# smd_missing_pulse_detector_sot23.net
KiCad netlist of a schematic drawn in EAGLE
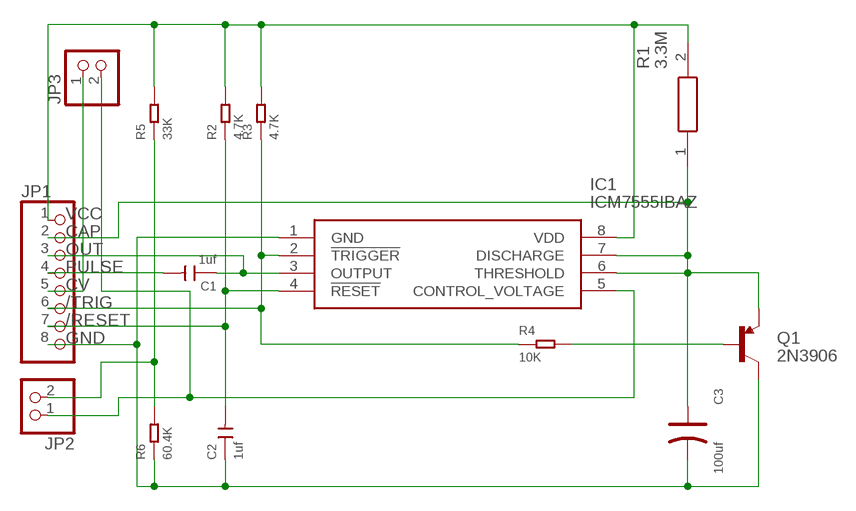
[diagram p0: schematic, sheet 1]

(export (version "E")
  (design (tool "Eeschema 10.0.6"))
  (components
    (comp (ref "C1")
      (value "1uf")
      (footprint "eagle-import:C0805")
      (fields (field (name "MPN") "CC0805KKX7R8BB105"))
      (libsource (lib "eagle-import") (part "CERAMIC-1UF-25V-10%-X7R(0805)"))
    )
    (comp (ref "C2")
      (value "1uf")
      (footprint "eagle-import:C0805")
      (fields (field (name "MPN") "CC0805KKX7R8BB105"))
      (libsource (lib "eagle-import") (part "CERAMIC-1UF-25V-10%-X7R(0805)"))
    )
    (comp (ref "C3")
      (value "100uf")
      (footprint "eagle-import:AVX-B")
      (fields (field (name "MPN") "TAJB107M010#NJ"))
      (libsource (lib "eagle-import") (part "TANTALUM-SMD-100UF-10V(AVX-B)"))
    )
    (comp (ref "IC1")
      (value "ICM7555IBAZ")
      (footprint "eagle-import:SOIC127P600X175-8N")
      (fields (field (name "MOUSER_PART_NUMBER") "968-ICM7555IBAZ"))
      (libsource (lib "eagle-import") (part "ICM7555IBAZ"))
    )
    (comp (ref "JP1")
      (value "PINHD-1X8")
      (footprint "eagle-import:1X08")
      (libsource (lib "eagle-import") (part "PINHD-1X8"))
    )
    (comp (ref "JP2")
      (value "PINHD-1X2")
      (footprint "eagle-import:1X02")
      (libsource (lib "eagle-import") (part "PINHD-1X2"))
    )
    (comp (ref "JP3")
      (value "PINHD-1X2")
      (footprint "eagle-import:1X02")
      (libsource (lib "eagle-import") (part "PINHD-1X2"))
    )
    (comp (ref "Q1")
      (value "2N3906")
      (footprint "eagle-import:SOT23-3")
      (libsource (lib "eagle-import") (part "TRANSISTOR_PNPPMBT3906"))
    )
    (comp (ref "R1")
      (value "3.3M")
      (footprint "eagle-import:RESC1608X50N")
      (fields
        (field (name "ARROW_PART_NUMBER") "CRCW06033M30FKEA")
        (field (name "MOUSER_PART_NUMBER") "71-CRCW06033M30FKEA")
      )
      (libsource (lib "eagle-import") (part "CRCW06033M30FKEA"))
    )
    (comp (ref "R2")
      (value "4.7K")
      (footprint "eagle-import:R0603")
      (fields (field (name "MPN") "RC0603JR-074K7L"))
      (libsource (lib "eagle-import") (part "SMD-RES-4.7K-5%-1/10W(0603)"))
    )
    (comp (ref "R3")
      (value "4.7K")
      (footprint "eagle-import:R0603")
      (fields (field (name "MPN") "RC0603JR-074K7L"))
      (libsource (lib "eagle-import") (part "SMD-RES-4.7K-5%-1/10W(0603)"))
    )
    (comp (ref "R4")
      (value "10K")
      (footprint "eagle-import:R0603")
      (fields (field (name "MPN") "RC0603FR-0710KL"))
      (libsource (lib "eagle-import") (part "SMD-RES-10K-1%-1/10W(0603)"))
    )
    (comp (ref "R5")
      (value "33K")
      (footprint "eagle-import:R0603")
      (fields (field (name "MPN") "RC0603JR-074K7L"))
      (libsource (lib "eagle-import") (part "SMD-RES-4.7K-5%-1/10W(0603)"))
    )
    (comp (ref "R6")
      (value "60.4K")
      (footprint "eagle-import:R0603")
      (fields (field (name "MPN") "RC0603JR-074K7L"))
      (libsource (lib "eagle-import") (part "SMD-RES-4.7K-5%-1/10W(0603)"))
    )
  )
  (nets
    (net (code "1") (name "/CAP") (class "Default")
      (node (ref "C3") (pin "+") (pinfunction "+_+") (pintype "passive"))
      (node (ref "IC1") (pin "6") (pinfunction "THRESHOLD_6") (pintype "bidirectional"))
      (node (ref "IC1") (pin "7") (pinfunction "DISCHARGE_7") (pintype "bidirectional"))
      (node (ref "JP1") (pin "2") (pinfunction "2_2") (pintype "passive"))
      (node (ref "Q1") (pin "2") (pinfunction "E_2") (pintype "passive"))
      (node (ref "R1") (pin "1") (pinfunction "1_1") (pintype "bidirectional"))
    )
    (net (code "2") (name "/CV") (class "Default")
      (node (ref "IC1") (pin "5") (pinfunction "CONTROL_VOLTAGE_5") (pintype "bidirectional"))
      (node (ref "JP2") (pin "1") (pinfunction "1_1") (pintype "passive"))
      (node (ref "JP3") (pin "2") (pinfunction "2_2") (pintype "passive"))
    )
    (net (code "3") (name "/GND") (class "Default")
      (node (ref "C2") (pin "1") (pinfunction "1_1") (pintype "passive"))
      (node (ref "C3") (pin "-") (pinfunction "-_-") (pintype "passive"))
      (node (ref "IC1") (pin "1") (pinfunction "GND_1") (pintype "bidirectional"))
      (node (ref "JP1") (pin "8") (pinfunction "8_8") (pintype "passive"))
      (node (ref "Q1") (pin "3") (pinfunction "C_3") (pintype "passive"))
      (node (ref "R6") (pin "1") (pinfunction "1_1") (pintype "passive"))
    )
    (net (code "4") (name "/OUT") (class "Default")
      (node (ref "C1") (pin "1") (pinfunction "1_1") (pintype "passive"))
      (node (ref "IC1") (pin "3") (pinfunction "OUTPUT_3") (pintype "bidirectional"))
      (node (ref "JP1") (pin "3") (pinfunction "3_3") (pintype "passive"))
    )
    (net (code "5") (name "/PULSE") (class "Default")
      (node (ref "C1") (pin "2") (pinfunction "2_2") (pintype "passive"))
      (node (ref "JP1") (pin "4") (pinfunction "4_4") (pintype "passive"))
    )
    (net (code "6") (name "/VCC") (class "Default")
      (node (ref "IC1") (pin "8") (pinfunction "VDD_8") (pintype "bidirectional"))
      (node (ref "JP1") (pin "1") (pinfunction "1_1") (pintype "passive"))
      (node (ref "R1") (pin "2") (pinfunction "2_2") (pintype "bidirectional"))
      (node (ref "R2") (pin "2") (pinfunction "2_2") (pintype "passive"))
      (node (ref "R3") (pin "2") (pinfunction "2_2") (pintype "passive"))
      (node (ref "R5") (pin "2") (pinfunction "2_2") (pintype "passive"))
    )
    (net (code "7") (name "/{slash}RESET") (class "Default")
      (node (ref "C2") (pin "2") (pinfunction "2_2") (pintype "passive"))
      (node (ref "IC1") (pin "4") (pinfunction "~{RESET}_4") (pintype "bidirectional"))
      (node (ref "JP1") (pin "7") (pinfunction "7_7") (pintype "passive"))
      (node (ref "R2") (pin "1") (pinfunction "1_1") (pintype "passive"))
    )
    (net (code "8") (name "/{slash}TRIG") (class "Default")
      (node (ref "IC1") (pin "2") (pinfunction "~{TRIGGER}_2") (pintype "bidirectional"))
      (node (ref "JP1") (pin "6") (pinfunction "6_6") (pintype "passive"))
      (node (ref "R3") (pin "1") (pinfunction "1_1") (pintype "passive"))
      (node (ref "R4") (pin "1") (pinfunction "1_1") (pintype "passive"))
    )
    (net (code "9") (name "Net-(JP1-Pad5)") (class "Default")
      (node (ref "JP1") (pin "5") (pinfunction "5_5") (pintype "passive"))
      (node (ref "JP3") (pin "1") (pinfunction "1_1") (pintype "passive"))
    )
    (net (code "10") (name "Net-(JP2-Pad2)") (class "Default")
      (node (ref "JP2") (pin "2") (pinfunction "2_2") (pintype "passive"))
      (node (ref "R5") (pin "1") (pinfunction "1_1") (pintype "passive"))
      (node (ref "R6") (pin "2") (pinfunction "2_2") (pintype "passive"))
    )
    (net (code "11") (name "Net-(Q1-B)") (class "Default")
      (node (ref "Q1") (pin "1") (pinfunction "B_1") (pintype "passive"))
      (node (ref "R4") (pin "2") (pinfunction "2_2") (pintype "passive"))
    )
  )
)
